# comcon_version_av2.net
KiCad netlist of a schematic drawn in EAGLE
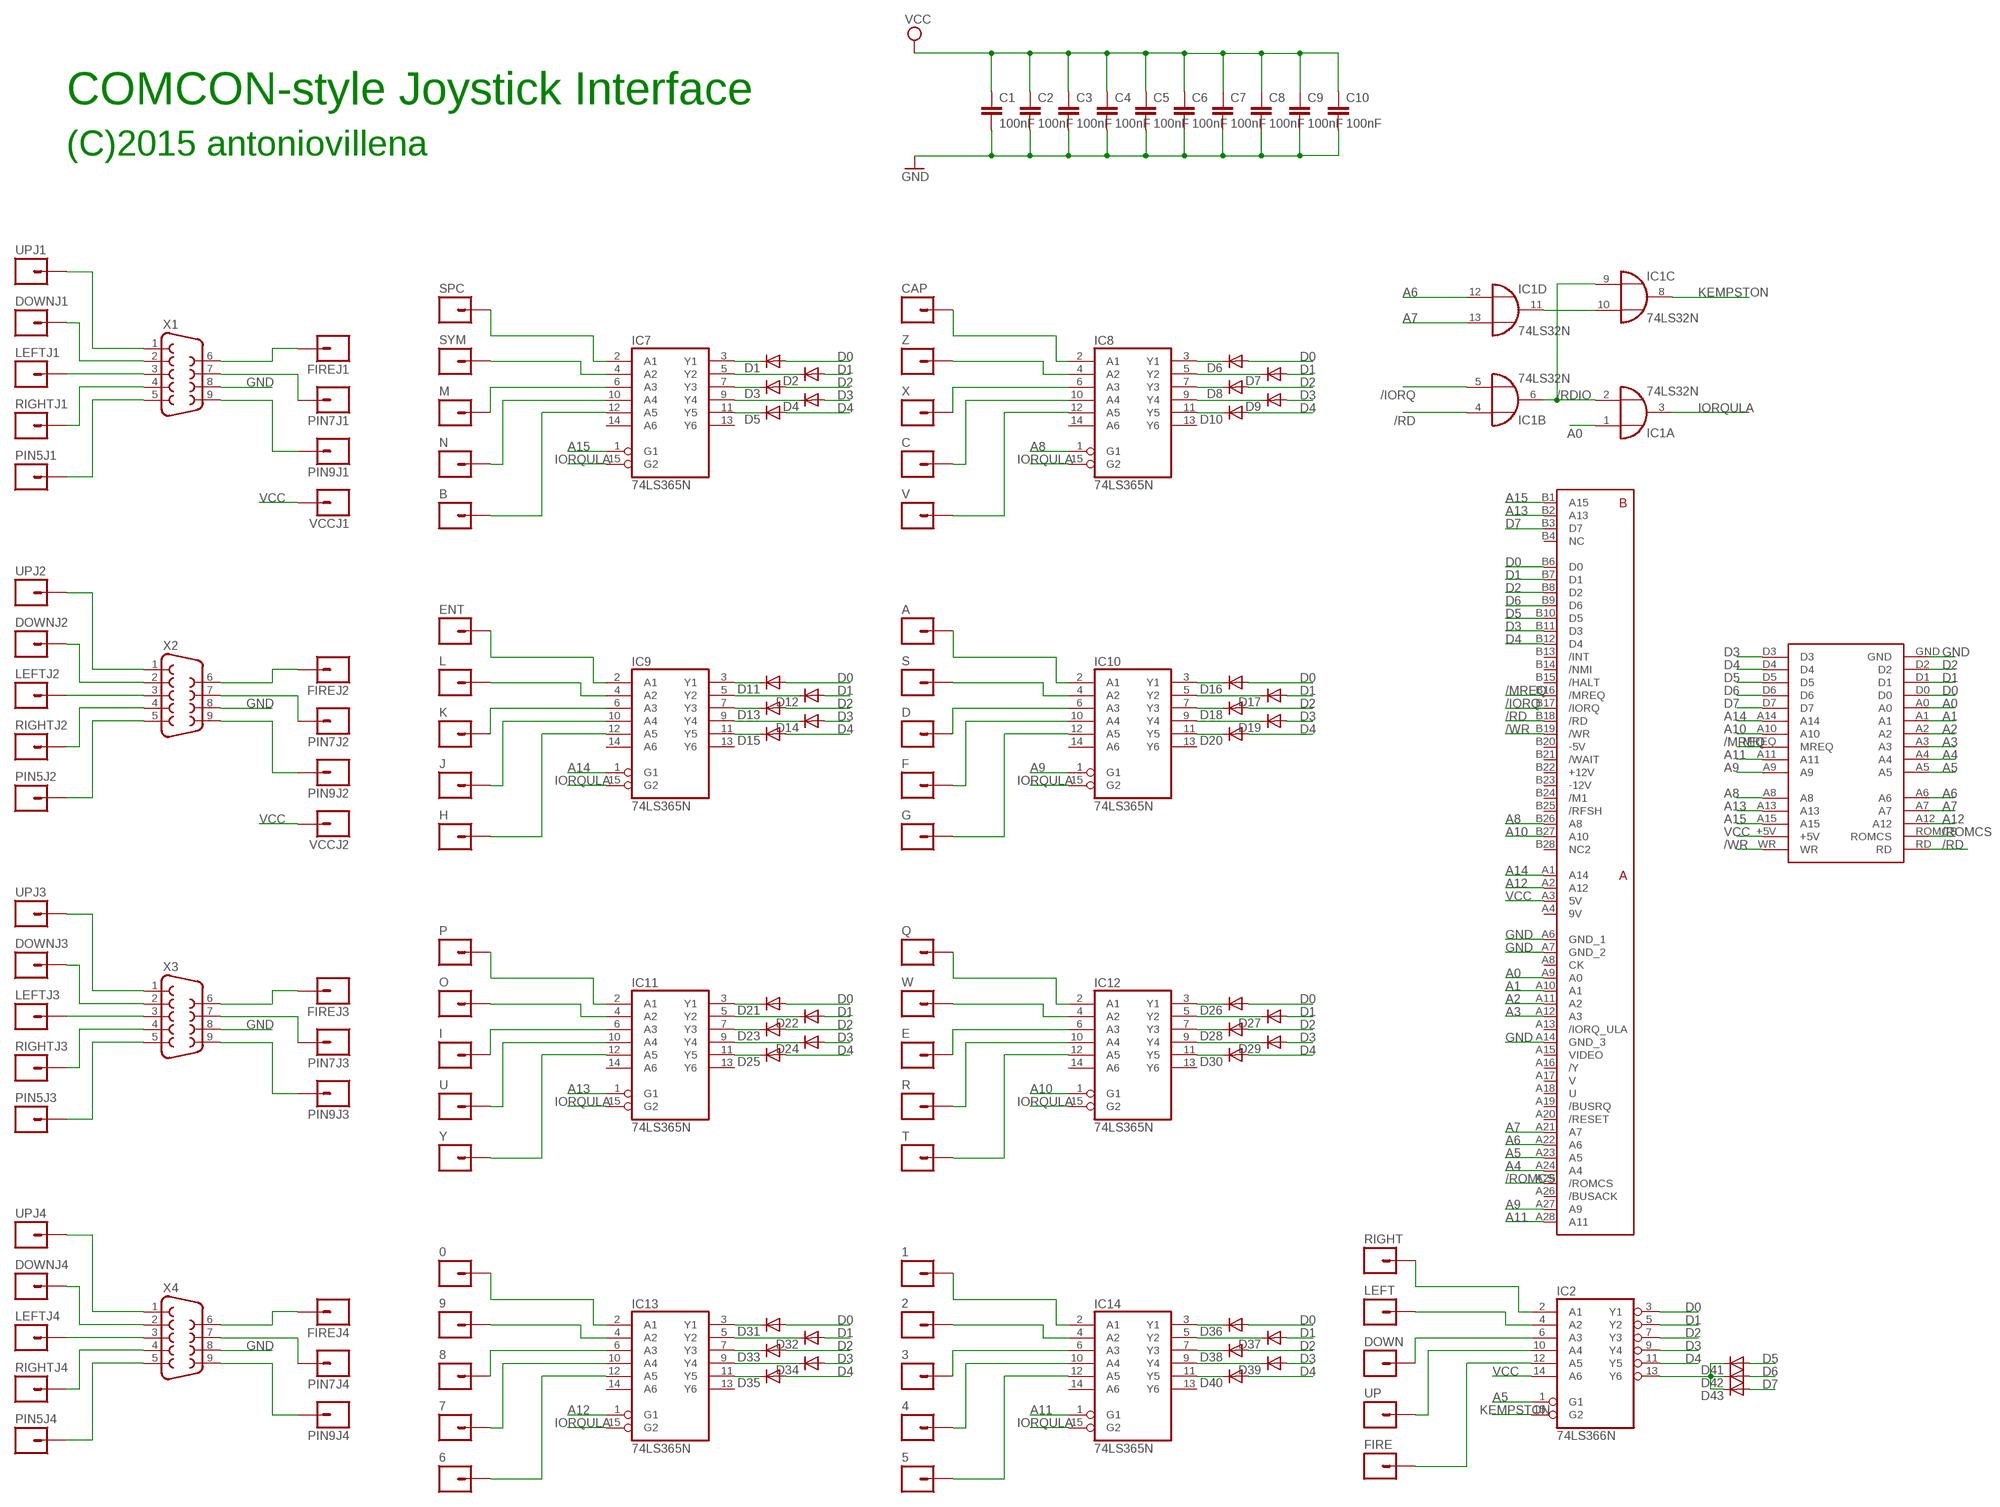
[diagram p0: schematic, sheet 1]

(export (version "E")
  (design (tool "Eeschema 10.0.6"))
  (components
    (comp (ref "0")
      (value "M01PTH")
      (footprint "eagle-import:1X01")
      (libsource (lib "eagle-import") (part "M01PTH"))
    )
    (comp (ref "1")
      (value "M01PTH")
      (footprint "eagle-import:1X01")
      (libsource (lib "eagle-import") (part "M01PTH"))
    )
    (comp (ref "2")
      (value "M01PTH")
      (footprint "eagle-import:1X01")
      (libsource (lib "eagle-import") (part "M01PTH"))
    )
    (comp (ref "3")
      (value "M01PTH")
      (footprint "eagle-import:1X01")
      (libsource (lib "eagle-import") (part "M01PTH"))
    )
    (comp (ref "4")
      (value "M01PTH")
      (footprint "eagle-import:1X01")
      (libsource (lib "eagle-import") (part "M01PTH"))
    )
    (comp (ref "5")
      (value "M01PTH")
      (footprint "eagle-import:1X01")
      (libsource (lib "eagle-import") (part "M01PTH"))
    )
    (comp (ref "6")
      (value "M01PTH")
      (footprint "eagle-import:1X01")
      (libsource (lib "eagle-import") (part "M01PTH"))
    )
    (comp (ref "7")
      (value "M01PTH")
      (footprint "eagle-import:1X01")
      (libsource (lib "eagle-import") (part "M01PTH"))
    )
    (comp (ref "8")
      (value "M01PTH")
      (footprint "eagle-import:1X01")
      (libsource (lib "eagle-import") (part "M01PTH"))
    )
    (comp (ref "9")
      (value "M01PTH")
      (footprint "eagle-import:1X01")
      (libsource (lib "eagle-import") (part "M01PTH"))
    )
    (comp (ref "A")
      (value "M01PTH")
      (footprint "eagle-import:1X01")
      (libsource (lib "eagle-import") (part "M01PTH"))
    )
    (comp (ref "B")
      (value "M01PTH")
      (footprint "eagle-import:1X01")
      (libsource (lib "eagle-import") (part "M01PTH"))
    )
    (comp (ref "C")
      (value "M01PTH")
      (footprint "eagle-import:1X01")
      (libsource (lib "eagle-import") (part "M01PTH"))
    )
    (comp (ref "C1")
      (value "100nF")
      (footprint "eagle-import:C050-025X075")
      (libsource (lib "eagle-import") (part "C-EU050-025X075"))
    )
    (comp (ref "C2")
      (value "100nF")
      (footprint "eagle-import:C050-025X075")
      (libsource (lib "eagle-import") (part "C-EU050-025X075"))
    )
    (comp (ref "C3")
      (value "100nF")
      (footprint "eagle-import:C050-025X075")
      (libsource (lib "eagle-import") (part "C-EU050-025X075"))
    )
    (comp (ref "C4")
      (value "100nF")
      (footprint "eagle-import:C050-025X075")
      (libsource (lib "eagle-import") (part "C-EU050-025X075"))
    )
    (comp (ref "C5")
      (value "100nF")
      (footprint "eagle-import:C050-025X075")
      (libsource (lib "eagle-import") (part "C-EU050-025X075"))
    )
    (comp (ref "C6")
      (value "100nF")
      (footprint "eagle-import:C050-025X075")
      (libsource (lib "eagle-import") (part "C-EU050-025X075"))
    )
    (comp (ref "C7")
      (value "100nF")
      (footprint "eagle-import:C050-025X075")
      (libsource (lib "eagle-import") (part "C-EU050-025X075"))
    )
    (comp (ref "C8")
      (value "100nF")
      (footprint "eagle-import:C050-025X075")
      (libsource (lib "eagle-import") (part "C-EU050-025X075"))
    )
    (comp (ref "C9")
      (value "100nF")
      (footprint "eagle-import:C050-025X075")
      (libsource (lib "eagle-import") (part "C-EU050-025X075"))
    )
    (comp (ref "C10")
      (value "100nF")
      (footprint "eagle-import:C050-025X075")
      (libsource (lib "eagle-import") (part "C-EU050-025X075"))
    )
    (comp (ref "CAP")
      (value "M01PTH")
      (footprint "eagle-import:1X01")
      (libsource (lib "eagle-import") (part "M01PTH"))
    )
    (comp (ref "D")
      (value "M01PTH")
      (footprint "eagle-import:1X01")
      (libsource (lib "eagle-import") (part "M01PTH"))
    )
    (comp (ref "D1")
      (value "1N4148DO35-7")
      (footprint "eagle-import:DO35-7")
      (libsource (lib "eagle-import") (part "1N4148DO35-7"))
    )
    (comp (ref "D2")
      (value "1N4148DO35-7")
      (footprint "eagle-import:DO35-7")
      (libsource (lib "eagle-import") (part "1N4148DO35-7"))
    )
    (comp (ref "D3")
      (value "1N4148DO35-7")
      (footprint "eagle-import:DO35-7")
      (libsource (lib "eagle-import") (part "1N4148DO35-7"))
    )
    (comp (ref "D4")
      (value "1N4148DO35-7")
      (footprint "eagle-import:DO35-7")
      (libsource (lib "eagle-import") (part "1N4148DO35-7"))
    )
    (comp (ref "D5")
      (value "1N4148DO35-7")
      (footprint "eagle-import:DO35-7")
      (libsource (lib "eagle-import") (part "1N4148DO35-7"))
    )
    (comp (ref "D6")
      (value "1N4148DO35-7")
      (footprint "eagle-import:DO35-7")
      (libsource (lib "eagle-import") (part "1N4148DO35-7"))
    )
    (comp (ref "D7")
      (value "1N4148DO35-7")
      (footprint "eagle-import:DO35-7")
      (libsource (lib "eagle-import") (part "1N4148DO35-7"))
    )
    (comp (ref "D8")
      (value "1N4148DO35-7")
      (footprint "eagle-import:DO35-7")
      (libsource (lib "eagle-import") (part "1N4148DO35-7"))
    )
    (comp (ref "D9")
      (value "1N4148DO35-7")
      (footprint "eagle-import:DO35-7")
      (libsource (lib "eagle-import") (part "1N4148DO35-7"))
    )
    (comp (ref "D10")
      (value "1N4148DO35-7")
      (footprint "eagle-import:DO35-7")
      (libsource (lib "eagle-import") (part "1N4148DO35-7"))
    )
    (comp (ref "D11")
      (value "1N4148DO35-7")
      (footprint "eagle-import:DO35-7")
      (libsource (lib "eagle-import") (part "1N4148DO35-7"))
    )
    (comp (ref "D12")
      (value "1N4148DO35-7")
      (footprint "eagle-import:DO35-7")
      (libsource (lib "eagle-import") (part "1N4148DO35-7"))
    )
    (comp (ref "D13")
      (value "1N4148DO35-7")
      (footprint "eagle-import:DO35-7")
      (libsource (lib "eagle-import") (part "1N4148DO35-7"))
    )
    (comp (ref "D14")
      (value "1N4148DO35-7")
      (footprint "eagle-import:DO35-7")
      (libsource (lib "eagle-import") (part "1N4148DO35-7"))
    )
    (comp (ref "D15")
      (value "1N4148DO35-7")
      (footprint "eagle-import:DO35-7")
      (libsource (lib "eagle-import") (part "1N4148DO35-7"))
    )
    (comp (ref "D16")
      (value "1N4148DO35-7")
      (footprint "eagle-import:DO35-7")
      (libsource (lib "eagle-import") (part "1N4148DO35-7"))
    )
    (comp (ref "D17")
      (value "1N4148DO35-7")
      (footprint "eagle-import:DO35-7")
      (libsource (lib "eagle-import") (part "1N4148DO35-7"))
    )
    (comp (ref "D18")
      (value "1N4148DO35-7")
      (footprint "eagle-import:DO35-7")
      (libsource (lib "eagle-import") (part "1N4148DO35-7"))
    )
    (comp (ref "D19")
      (value "1N4148DO35-7")
      (footprint "eagle-import:DO35-7")
      (libsource (lib "eagle-import") (part "1N4148DO35-7"))
    )
    (comp (ref "D20")
      (value "1N4148DO35-7")
      (footprint "eagle-import:DO35-7")
      (libsource (lib "eagle-import") (part "1N4148DO35-7"))
    )
    (comp (ref "D21")
      (value "1N4148DO35-7")
      (footprint "eagle-import:DO35-7")
      (libsource (lib "eagle-import") (part "1N4148DO35-7"))
    )
    (comp (ref "D22")
      (value "1N4148DO35-7")
      (footprint "eagle-import:DO35-7")
      (libsource (lib "eagle-import") (part "1N4148DO35-7"))
    )
    (comp (ref "D23")
      (value "1N4148DO35-7")
      (footprint "eagle-import:DO35-7")
      (libsource (lib "eagle-import") (part "1N4148DO35-7"))
    )
    (comp (ref "D24")
      (value "1N4148DO35-7")
      (footprint "eagle-import:DO35-7")
      (libsource (lib "eagle-import") (part "1N4148DO35-7"))
    )
    (comp (ref "D25")
      (value "1N4148DO35-7")
      (footprint "eagle-import:DO35-7")
      (libsource (lib "eagle-import") (part "1N4148DO35-7"))
    )
    (comp (ref "D26")
      (value "1N4148DO35-7")
      (footprint "eagle-import:DO35-7")
      (libsource (lib "eagle-import") (part "1N4148DO35-7"))
    )
    (comp (ref "D27")
      (value "1N4148DO35-7")
      (footprint "eagle-import:DO35-7")
      (libsource (lib "eagle-import") (part "1N4148DO35-7"))
    )
    (comp (ref "D28")
      (value "1N4148DO35-7")
      (footprint "eagle-import:DO35-7")
      (libsource (lib "eagle-import") (part "1N4148DO35-7"))
    )
    (comp (ref "D29")
      (value "1N4148DO35-7")
      (footprint "eagle-import:DO35-7")
      (libsource (lib "eagle-import") (part "1N4148DO35-7"))
    )
    (comp (ref "D30")
      (value "1N4148DO35-7")
      (footprint "eagle-import:DO35-7")
      (libsource (lib "eagle-import") (part "1N4148DO35-7"))
    )
    (comp (ref "D31")
      (value "1N4148DO35-7")
      (footprint "eagle-import:DO35-7")
      (libsource (lib "eagle-import") (part "1N4148DO35-7"))
    )
    (comp (ref "D32")
      (value "1N4148DO35-7")
      (footprint "eagle-import:DO35-7")
      (libsource (lib "eagle-import") (part "1N4148DO35-7"))
    )
    (comp (ref "D33")
      (value "1N4148DO35-7")
      (footprint "eagle-import:DO35-7")
      (libsource (lib "eagle-import") (part "1N4148DO35-7"))
    )
    (comp (ref "D34")
      (value "1N4148DO35-7")
      (footprint "eagle-import:DO35-7")
      (libsource (lib "eagle-import") (part "1N4148DO35-7"))
    )
    (comp (ref "D35")
      (value "1N4148DO35-7")
      (footprint "eagle-import:DO35-7")
      (libsource (lib "eagle-import") (part "1N4148DO35-7"))
    )
    (comp (ref "D36")
      (value "1N4148DO35-7")
      (footprint "eagle-import:DO35-7")
      (libsource (lib "eagle-import") (part "1N4148DO35-7"))
    )
    (comp (ref "D37")
      (value "1N4148DO35-7")
      (footprint "eagle-import:DO35-7")
      (libsource (lib "eagle-import") (part "1N4148DO35-7"))
    )
    (comp (ref "D38")
      (value "1N4148DO35-7")
      (footprint "eagle-import:DO35-7")
      (libsource (lib "eagle-import") (part "1N4148DO35-7"))
    )
    (comp (ref "D39")
      (value "1N4148DO35-7")
      (footprint "eagle-import:DO35-7")
      (libsource (lib "eagle-import") (part "1N4148DO35-7"))
    )
    (comp (ref "D40")
      (value "1N4148DO35-7")
      (footprint "eagle-import:DO35-7")
      (libsource (lib "eagle-import") (part "1N4148DO35-7"))
    )
    (comp (ref "D41")
      (value "1N4148DO35-10")
      (footprint "eagle-import:DO35-10")
      (libsource (lib "eagle-import") (part "1N4148DO35-10"))
    )
    (comp (ref "D42")
      (value "1N4148DO35-10")
      (footprint "eagle-import:DO35-10")
      (libsource (lib "eagle-import") (part "1N4148DO35-10"))
    )
    (comp (ref "D43")
      (value "1N4148DO35-7")
      (footprint "eagle-import:DO35-7")
      (libsource (lib "eagle-import") (part "1N4148DO35-7"))
    )
    (comp (ref "DOWN")
      (value "M01PTH")
      (footprint "eagle-import:1X01")
      (libsource (lib "eagle-import") (part "M01PTH"))
    )
    (comp (ref "DOWNJ1")
      (value "M01PTH")
      (footprint "eagle-import:1X01")
      (libsource (lib "eagle-import") (part "M01PTH"))
    )
    (comp (ref "DOWNJ2")
      (value "M01PTH")
      (footprint "eagle-import:1X01")
      (libsource (lib "eagle-import") (part "M01PTH"))
    )
    (comp (ref "DOWNJ3")
      (value "M01PTH")
      (footprint "eagle-import:1X01")
      (libsource (lib "eagle-import") (part "M01PTH"))
    )
    (comp (ref "DOWNJ4")
      (value "M01PTH")
      (footprint "eagle-import:1X01")
      (libsource (lib "eagle-import") (part "M01PTH"))
    )
    (comp (ref "E")
      (value "M01PTH")
      (footprint "eagle-import:1X01")
      (libsource (lib "eagle-import") (part "M01PTH"))
    )
    (comp (ref "ENT")
      (value "M01PTH")
      (footprint "eagle-import:1X01")
      (libsource (lib "eagle-import") (part "M01PTH"))
    )
    (comp (ref "F")
      (value "M01PTH")
      (footprint "eagle-import:1X01")
      (libsource (lib "eagle-import") (part "M01PTH"))
    )
    (comp (ref "FIRE")
      (value "M01PTH")
      (footprint "eagle-import:1X01")
      (libsource (lib "eagle-import") (part "M01PTH"))
    )
    (comp (ref "FIREJ1")
      (value "M01PTH")
      (footprint "eagle-import:1X01")
      (libsource (lib "eagle-import") (part "M01PTH"))
    )
    (comp (ref "FIREJ2")
      (value "M01PTH")
      (footprint "eagle-import:1X01")
      (libsource (lib "eagle-import") (part "M01PTH"))
    )
    (comp (ref "FIREJ3")
      (value "M01PTH")
      (footprint "eagle-import:1X01")
      (libsource (lib "eagle-import") (part "M01PTH"))
    )
    (comp (ref "FIREJ4")
      (value "M01PTH")
      (footprint "eagle-import:1X01")
      (libsource (lib "eagle-import") (part "M01PTH"))
    )
    (comp (ref "G")
      (value "M01PTH")
      (footprint "eagle-import:1X01")
      (libsource (lib "eagle-import") (part "M01PTH"))
    )
    (comp (ref "H")
      (value "M01PTH")
      (footprint "eagle-import:1X01")
      (libsource (lib "eagle-import") (part "M01PTH"))
    )
    (comp (ref "I")
      (value "M01PTH")
      (footprint "eagle-import:1X01")
      (libsource (lib "eagle-import") (part "M01PTH"))
    )
    (comp (ref "IC1")
      (value "74LS32N")
      (footprint "eagle-import:DIL14")
      (libsource (lib "eagle-import") (part "7432NLS"))
    )
    (comp (ref "IC2")
      (value "74LS366N")
      (footprint "eagle-import:DIL16")
      (libsource (lib "eagle-import") (part "74366NLS"))
    )
    (comp (ref "IC7")
      (value "74LS365N")
      (footprint "eagle-import:DIL16")
      (libsource (lib "eagle-import") (part "74365NHC"))
    )
    (comp (ref "IC8")
      (value "74LS365N")
      (footprint "eagle-import:DIL16")
      (libsource (lib "eagle-import") (part "74365NHC"))
    )
    (comp (ref "IC9")
      (value "74LS365N")
      (footprint "eagle-import:DIL16")
      (libsource (lib "eagle-import") (part "74365NHC"))
    )
    (comp (ref "IC10")
      (value "74LS365N")
      (footprint "eagle-import:DIL16")
      (libsource (lib "eagle-import") (part "74365NHC"))
    )
    (comp (ref "IC11")
      (value "74LS365N")
      (footprint "eagle-import:DIL16")
      (libsource (lib "eagle-import") (part "74365NHC"))
    )
    (comp (ref "IC12")
      (value "74LS365N")
      (footprint "eagle-import:DIL16")
      (libsource (lib "eagle-import") (part "74365NHC"))
    )
    (comp (ref "IC13")
      (value "74LS365N")
      (footprint "eagle-import:DIL16")
      (libsource (lib "eagle-import") (part "74365NHC"))
    )
    (comp (ref "IC14")
      (value "74LS365N")
      (footprint "eagle-import:DIL16")
      (libsource (lib "eagle-import") (part "74365NHC"))
    )
    (comp (ref "J")
      (value "M01PTH")
      (footprint "eagle-import:1X01")
      (libsource (lib "eagle-import") (part "M01PTH"))
    )
    (comp (ref "K")
      (value "M01PTH")
      (footprint "eagle-import:1X01")
      (libsource (lib "eagle-import") (part "M01PTH"))
    )
    (comp (ref "L")
      (value "M01PTH")
      (footprint "eagle-import:1X01")
      (libsource (lib "eagle-import") (part "M01PTH"))
    )
    (comp (ref "LEFT")
      (value "M01PTH")
      (footprint "eagle-import:1X01")
      (libsource (lib "eagle-import") (part "M01PTH"))
    )
    (comp (ref "LEFTJ1")
      (value "M01PTH")
      (footprint "eagle-import:1X01")
      (libsource (lib "eagle-import") (part "M01PTH"))
    )
    (comp (ref "LEFTJ2")
      (value "M01PTH")
      (footprint "eagle-import:1X01")
      (libsource (lib "eagle-import") (part "M01PTH"))
    )
    (comp (ref "LEFTJ3")
      (value "M01PTH")
      (footprint "eagle-import:1X01")
      (libsource (lib "eagle-import") (part "M01PTH"))
    )
    (comp (ref "LEFTJ4")
      (value "M01PTH")
      (footprint "eagle-import:1X01")
      (libsource (lib "eagle-import") (part "M01PTH"))
    )
    (comp (ref "M")
      (value "M01PTH")
      (footprint "eagle-import:1X01")
      (libsource (lib "eagle-import") (part "M01PTH"))
    )
    (comp (ref "N")
      (value "M01PTH")
      (footprint "eagle-import:1X01")
      (libsource (lib "eagle-import") (part "M01PTH"))
    )
    (comp (ref "O")
      (value "M01PTH")
      (footprint "eagle-import:1X01")
      (libsource (lib "eagle-import") (part "M01PTH"))
    )
    (comp (ref "P")
      (value "M01PTH")
      (footprint "eagle-import:1X01")
      (libsource (lib "eagle-import") (part "M01PTH"))
    )
    (comp (ref "PIN5J1")
      (value "M01PTH")
      (footprint "eagle-import:1X01")
      (libsource (lib "eagle-import") (part "M01PTH"))
    )
    (comp (ref "PIN5J2")
      (value "M01PTH")
      (footprint "eagle-import:1X01")
      (libsource (lib "eagle-import") (part "M01PTH"))
    )
    (comp (ref "PIN5J3")
      (value "M01PTH")
      (footprint "eagle-import:1X01")
      (libsource (lib "eagle-import") (part "M01PTH"))
    )
    (comp (ref "PIN5J4")
      (value "M01PTH")
      (footprint "eagle-import:1X01")
      (libsource (lib "eagle-import") (part "M01PTH"))
    )
    (comp (ref "PIN7J1")
      (value "M01PTH")
      (footprint "eagle-import:1X01")
      (libsource (lib "eagle-import") (part "M01PTH"))
    )
    (comp (ref "PIN7J2")
      (value "M01PTH")
      (footprint "eagle-import:1X01")
      (libsource (lib "eagle-import") (part "M01PTH"))
    )
    (comp (ref "PIN7J3")
      (value "M01PTH")
      (footprint "eagle-import:1X01")
      (libsource (lib "eagle-import") (part "M01PTH"))
    )
    (comp (ref "PIN7J4")
      (value "M01PTH")
      (footprint "eagle-import:1X01")
      (libsource (lib "eagle-import") (part "M01PTH"))
    )
    (comp (ref "PIN9J1")
      (value "M01PTH")
      (footprint "eagle-import:1X01")
      (libsource (lib "eagle-import") (part "M01PTH"))
    )
    (comp (ref "PIN9J2")
      (value "M01PTH")
      (footprint "eagle-import:1X01")
      (libsource (lib "eagle-import") (part "M01PTH"))
    )
    (comp (ref "PIN9J3")
      (value "M01PTH")
      (footprint "eagle-import:1X01")
      (libsource (lib "eagle-import") (part "M01PTH"))
    )
    (comp (ref "PIN9J4")
      (value "M01PTH")
      (footprint "eagle-import:1X01")
      (libsource (lib "eagle-import") (part "M01PTH"))
    )
    (comp (ref "Q")
      (value "M01PTH")
      (footprint "eagle-import:1X01")
      (libsource (lib "eagle-import") (part "M01PTH"))
    )
    (comp (ref "R")
      (value "M01PTH")
      (footprint "eagle-import:1X01")
      (libsource (lib "eagle-import") (part "M01PTH"))
    )
    (comp (ref "RIGHT")
      (value "M01PTH")
      (footprint "eagle-import:1X01")
      (libsource (lib "eagle-import") (part "M01PTH"))
    )
    (comp (ref "RIGHTJ1")
      (value "M01PTH")
      (footprint "eagle-import:1X01")
      (libsource (lib "eagle-import") (part "M01PTH"))
    )
    (comp (ref "RIGHTJ2")
      (value "M01PTH")
      (footprint "eagle-import:1X01")
      (libsource (lib "eagle-import") (part "M01PTH"))
    )
    (comp (ref "RIGHTJ3")
      (value "M01PTH")
      (footprint "eagle-import:1X01")
      (libsource (lib "eagle-import") (part "M01PTH"))
    )
    (comp (ref "RIGHTJ4")
      (value "M01PTH")
      (footprint "eagle-import:1X01")
      (libsource (lib "eagle-import") (part "M01PTH"))
    )
    (comp (ref "S")
      (value "M01PTH")
      (footprint "eagle-import:1X01")
      (libsource (lib "eagle-import") (part "M01PTH"))
    )
    (comp (ref "SPC")
      (value "M01PTH")
      (footprint "eagle-import:1X01")
      (libsource (lib "eagle-import") (part "M01PTH"))
    )
    (comp (ref "SYM")
      (value "M01PTH")
      (footprint "eagle-import:1X01")
      (libsource (lib "eagle-import") (part "M01PTH"))
    )
    (comp (ref "T")
      (value "M01PTH")
      (footprint "eagle-import:1X01")
      (libsource (lib "eagle-import") (part "M01PTH"))
    )
    (comp (ref "U")
      (value "M01PTH")
      (footprint "eagle-import:1X01")
      (libsource (lib "eagle-import") (part "M01PTH"))
    )
    (comp (ref "U$1")
      (value "ZX_CARTRIDGE")
      (footprint "eagle-import:ZX_CARTRIDGE")
      (libsource (lib "eagle-import") (part "ZX_CARTRIDGE"))
    )
    (comp (ref "U$3")
      (value "ZXSP_ED2X28_SPE")
      (footprint "eagle-import:2X28_SPE")
      (libsource (lib "eagle-import") (part "ZXSP_ED2X28_SPE"))
    )
    (comp (ref "UP")
      (value "M01PTH")
      (footprint "eagle-import:1X01")
      (libsource (lib "eagle-import") (part "M01PTH"))
    )
    (comp (ref "UPJ1")
      (value "M01PTH")
      (footprint "eagle-import:1X01")
      (libsource (lib "eagle-import") (part "M01PTH"))
    )
    (comp (ref "UPJ2")
      (value "M01PTH")
      (footprint "eagle-import:1X01")
      (libsource (lib "eagle-import") (part "M01PTH"))
    )
    (comp (ref "UPJ3")
      (value "M01PTH")
      (footprint "eagle-import:1X01")
      (libsource (lib "eagle-import") (part "M01PTH"))
    )
    (comp (ref "UPJ4")
      (value "M01PTH")
      (footprint "eagle-import:1X01")
      (libsource (lib "eagle-import") (part "M01PTH"))
    )
    (comp (ref "V")
      (value "M01PTH")
      (footprint "eagle-import:1X01")
      (libsource (lib "eagle-import") (part "M01PTH"))
    )
    (comp (ref "VCCJ1")
      (value "M01PTH")
      (footprint "eagle-import:1X01")
      (libsource (lib "eagle-import") (part "M01PTH"))
    )
    (comp (ref "VCCJ2")
      (value "M01PTH")
      (footprint "eagle-import:1X01")
      (libsource (lib "eagle-import") (part "M01PTH"))
    )
    (comp (ref "W")
      (value "M01PTH")
      (footprint "eagle-import:1X01")
      (libsource (lib "eagle-import") (part "M01PTH"))
    )
    (comp (ref "X")
      (value "M01PTH")
      (footprint "eagle-import:1X01")
      (libsource (lib "eagle-import") (part "M01PTH"))
    )
    (comp (ref "X1")
      (value "F09D")
      (footprint "eagle-import:F09D")
      (libsource (lib "eagle-import") (part "F09D"))
    )
    (comp (ref "X2")
      (value "F09D")
      (footprint "eagle-import:F09D")
      (libsource (lib "eagle-import") (part "F09D"))
    )
    (comp (ref "X3")
      (value "F09D")
      (footprint "eagle-import:F09D")
      (libsource (lib "eagle-import") (part "F09D"))
    )
    (comp (ref "X4")
      (value "F09D")
      (footprint "eagle-import:F09D")
      (libsource (lib "eagle-import") (part "F09D"))
    )
    (comp (ref "Y")
      (value "M01PTH")
      (footprint "eagle-import:1X01")
      (libsource (lib "eagle-import") (part "M01PTH"))
    )
    (comp (ref "Z")
      (value "M01PTH")
      (footprint "eagle-import:1X01")
      (libsource (lib "eagle-import") (part "M01PTH"))
    )
  )
  (nets
    (net (code "1") (name "/+12V") (class "Default")
      (node (ref "U$3") (pin "B22") (pinfunction "+12V_B22") (pintype "power_in"))
    )
    (net (code "2") (name "/-5V") (class "Default")
      (node (ref "U$3") (pin "B20") (pinfunction "-5V_B20") (pintype "power_in"))
    )
    (net (code "3") (name "/-12V") (class "Default")
      (node (ref "U$3") (pin "B23") (pinfunction "-12V_B23") (pintype "power_in"))
    )
    (net (code "4") (name "/9V") (class "Default")
      (node (ref "U$3") (pin "A4") (pinfunction "9V_A4") (pintype "power_in"))
    )
    (net (code "5") (name "/A0") (class "Default")
      (node (ref "IC1") (pin "1") (pinfunction "I0_1") (pintype "input"))
      (node (ref "U$1") (pin "A0") (pinfunction "A0_A0") (pintype "bidirectional"))
      (node (ref "U$3") (pin "A9") (pinfunction "A0_A9") (pintype "bidirectional"))
    )
    (net (code "6") (name "/A1") (class "Default")
      (node (ref "U$1") (pin "A1") (pinfunction "A1_A1") (pintype "bidirectional"))
      (node (ref "U$3") (pin "A10") (pinfunction "A1_A10") (pintype "bidirectional"))
    )
    (net (code "7") (name "/A2") (class "Default")
      (node (ref "U$1") (pin "A2") (pinfunction "A2_A2") (pintype "bidirectional"))
      (node (ref "U$3") (pin "A11") (pinfunction "A2_A11") (pintype "bidirectional"))
    )
    (net (code "8") (name "/A3") (class "Default")
      (node (ref "U$1") (pin "A3") (pinfunction "A3_A3") (pintype "bidirectional"))
      (node (ref "U$3") (pin "A12") (pinfunction "A3_A12") (pintype "bidirectional"))
    )
    (net (code "9") (name "/A4") (class "Default")
      (node (ref "U$1") (pin "A4") (pinfunction "A4_A4") (pintype "bidirectional"))
      (node (ref "U$3") (pin "A24") (pinfunction "A4_A24") (pintype "bidirectional"))
    )
    (net (code "10") (name "/A5") (class "Default")
      (node (ref "IC2") (pin "1") (pinfunction "G1_1") (pintype "input"))
      (node (ref "U$1") (pin "A5") (pinfunction "A5_A5") (pintype "bidirectional"))
      (node (ref "U$3") (pin "A23") (pinfunction "A5_A23") (pintype "bidirectional"))
    )
    (net (code "11") (name "/A6") (class "Default")
      (node (ref "IC1") (pin "12") (pinfunction "I0_12") (pintype "input"))
      (node (ref "U$1") (pin "A6") (pinfunction "A6_A6") (pintype "bidirectional"))
      (node (ref "U$3") (pin "A22") (pinfunction "A6_A22") (pintype "bidirectional"))
    )
    (net (code "12") (name "/A7") (class "Default")
      (node (ref "IC1") (pin "13") (pinfunction "I1_13") (pintype "input"))
      (node (ref "U$1") (pin "A7") (pinfunction "A7_A7") (pintype "bidirectional"))
      (node (ref "U$3") (pin "A21") (pinfunction "A7_A21") (pintype "bidirectional"))
    )
    (net (code "13") (name "/A8") (class "Default")
      (node (ref "IC8") (pin "1") (pinfunction "G1_1") (pintype "input"))
      (node (ref "U$1") (pin "A8") (pinfunction "A8_A8") (pintype "bidirectional"))
      (node (ref "U$3") (pin "B26") (pinfunction "A8_B26") (pintype "bidirectional"))
    )
    (net (code "14") (name "/A9") (class "Default")
      (node (ref "IC10") (pin "1") (pinfunction "G1_1") (pintype "input"))
      (node (ref "U$1") (pin "A9") (pinfunction "A9_A9") (pintype "bidirectional"))
      (node (ref "U$3") (pin "A27") (pinfunction "A9_A27") (pintype "bidirectional"))
    )
    (net (code "15") (name "/A10") (class "Default")
      (node (ref "IC12") (pin "1") (pinfunction "G1_1") (pintype "input"))
      (node (ref "U$1") (pin "A10") (pinfunction "A10_A10") (pintype "bidirectional"))
      (node (ref "U$3") (pin "B27") (pinfunction "A10_B27") (pintype "bidirectional"))
    )
    (net (code "16") (name "/A11") (class "Default")
      (node (ref "IC14") (pin "1") (pinfunction "G1_1") (pintype "input"))
      (node (ref "U$1") (pin "A11") (pinfunction "A11_A11") (pintype "bidirectional"))
      (node (ref "U$3") (pin "A28") (pinfunction "A11_A28") (pintype "bidirectional"))
    )
    (net (code "17") (name "/A12") (class "Default")
      (node (ref "IC13") (pin "1") (pinfunction "G1_1") (pintype "input"))
      (node (ref "U$1") (pin "A12") (pinfunction "A12_A12") (pintype "bidirectional"))
      (node (ref "U$3") (pin "A2") (pinfunction "A12_A2") (pintype "bidirectional"))
    )
    (net (code "18") (name "/A13") (class "Default")
      (node (ref "IC11") (pin "1") (pinfunction "G1_1") (pintype "input"))
      (node (ref "U$1") (pin "A13") (pinfunction "A13_A13") (pintype "bidirectional"))
      (node (ref "U$3") (pin "B2") (pinfunction "A13_B2") (pintype "bidirectional"))
    )
    (net (code "19") (name "/A14") (class "Default")
      (node (ref "IC9") (pin "1") (pinfunction "G1_1") (pintype "input"))
      (node (ref "U$1") (pin "A14") (pinfunction "A14_A14") (pintype "bidirectional"))
      (node (ref "U$3") (pin "A1") (pinfunction "A14_A1") (pintype "bidirectional"))
    )
    (net (code "20") (name "/A15") (class "Default")
      (node (ref "IC7") (pin "1") (pinfunction "G1_1") (pintype "input"))
      (node (ref "U$1") (pin "A15") (pinfunction "A15_A15") (pintype "bidirectional"))
      (node (ref "U$3") (pin "B1") (pinfunction "A15_B1") (pintype "bidirectional"))
    )
    (net (code "21") (name "/D0") (class "Default")
      (node (ref "D1") (pin "A") (pinfunction "A_A") (pintype "passive"))
      (node (ref "D11") (pin "A") (pinfunction "A_A") (pintype "passive"))
      (node (ref "D16") (pin "A") (pinfunction "A_A") (pintype "passive"))
      (node (ref "D21") (pin "A") (pinfunction "A_A") (pintype "passive"))
      (node (ref "D26") (pin "A") (pinfunction "A_A") (pintype "passive"))
      (node (ref "D31") (pin "A") (pinfunction "A_A") (pintype "passive"))
      (node (ref "D36") (pin "A") (pinfunction "A_A") (pintype "passive"))
      (node (ref "D6") (pin "A") (pinfunction "A_A") (pintype "passive"))
      (node (ref "IC2") (pin "3") (pinfunction "Y1_3") (pintype "tri_state"))
      (node (ref "U$1") (pin "D0") (pinfunction "D0_D0") (pintype "bidirectional"))
      (node (ref "U$3") (pin "B6") (pinfunction "D0_B6") (pintype "bidirectional"))
    )
    (net (code "22") (name "/D1") (class "Default")
      (node (ref "D12") (pin "A") (pinfunction "A_A") (pintype "passive"))
      (node (ref "D17") (pin "A") (pinfunction "A_A") (pintype "passive"))
      (node (ref "D2") (pin "A") (pinfunction "A_A") (pintype "passive"))
      (node (ref "D22") (pin "A") (pinfunction "A_A") (pintype "passive"))
      (node (ref "D27") (pin "A") (pinfunction "A_A") (pintype "passive"))
      (node (ref "D32") (pin "A") (pinfunction "A_A") (pintype "passive"))
      (node (ref "D37") (pin "A") (pinfunction "A_A") (pintype "passive"))
      (node (ref "D7") (pin "A") (pinfunction "A_A") (pintype "passive"))
      (node (ref "IC2") (pin "5") (pinfunction "Y2_5") (pintype "tri_state"))
      (node (ref "U$1") (pin "D1") (pinfunction "D1_D1") (pintype "bidirectional"))
      (node (ref "U$3") (pin "B7") (pinfunction "D1_B7") (pintype "bidirectional"))
    )
    (net (code "23") (name "/D2") (class "Default")
      (node (ref "D13") (pin "A") (pinfunction "A_A") (pintype "passive"))
      (node (ref "D18") (pin "A") (pinfunction "A_A") (pintype "passive"))
      (node (ref "D23") (pin "A") (pinfunction "A_A") (pintype "passive"))
      (node (ref "D28") (pin "A") (pinfunction "A_A") (pintype "passive"))
      (node (ref "D3") (pin "A") (pinfunction "A_A") (pintype "passive"))
      (node (ref "D33") (pin "A") (pinfunction "A_A") (pintype "passive"))
      (node (ref "D38") (pin "A") (pinfunction "A_A") (pintype "passive"))
      (node (ref "D8") (pin "A") (pinfunction "A_A") (pintype "passive"))
      (node (ref "IC2") (pin "7") (pinfunction "Y3_7") (pintype "tri_state"))
      (node (ref "U$1") (pin "D2") (pinfunction "D2_D2") (pintype "bidirectional"))
      (node (ref "U$3") (pin "B8") (pinfunction "D2_B8") (pintype "bidirectional"))
    )
    (net (code "24") (name "/D3") (class "Default")
      (node (ref "D14") (pin "A") (pinfunction "A_A") (pintype "passive"))
      (node (ref "D19") (pin "A") (pinfunction "A_A") (pintype "passive"))
      (node (ref "D24") (pin "A") (pinfunction "A_A") (pintype "passive"))
      (node (ref "D29") (pin "A") (pinfunction "A_A") (pintype "passive"))
      (node (ref "D34") (pin "A") (pinfunction "A_A") (pintype "passive"))
      (node (ref "D39") (pin "A") (pinfunction "A_A") (pintype "passive"))
      (node (ref "D4") (pin "A") (pinfunction "A_A") (pintype "passive"))
      (node (ref "D9") (pin "A") (pinfunction "A_A") (pintype "passive"))
      (node (ref "IC2") (pin "9") (pinfunction "Y4_9") (pintype "tri_state"))
      (node (ref "U$1") (pin "D3") (pinfunction "D3_D3") (pintype "bidirectional"))
      (node (ref "U$3") (pin "B11") (pinfunction "D3_B11") (pintype "bidirectional"))
    )
    (net (code "25") (name "/D4") (class "Default")
      (node (ref "D10") (pin "A") (pinfunction "A_A") (pintype "passive"))
      (node (ref "D15") (pin "A") (pinfunction "A_A") (pintype "passive"))
      (node (ref "D20") (pin "A") (pinfunction "A_A") (pintype "passive"))
      (node (ref "D25") (pin "A") (pinfunction "A_A") (pintype "passive"))
      (node (ref "D30") (pin "A") (pinfunction "A_A") (pintype "passive"))
      (node (ref "D35") (pin "A") (pinfunction "A_A") (pintype "passive"))
      (node (ref "D40") (pin "A") (pinfunction "A_A") (pintype "passive"))
      (node (ref "D5") (pin "A") (pinfunction "A_A") (pintype "passive"))
      (node (ref "IC2") (pin "11") (pinfunction "Y5_11") (pintype "tri_state"))
      (node (ref "U$1") (pin "D4") (pinfunction "D4_D4") (pintype "bidirectional"))
      (node (ref "U$3") (pin "B12") (pinfunction "D4_B12") (pintype "bidirectional"))
    )
    (net (code "26") (name "/D5") (class "Default")
      (node (ref "D41") (pin "A") (pinfunction "A_A") (pintype "passive"))
      (node (ref "U$1") (pin "D5") (pinfunction "D5_D5") (pintype "bidirectional"))
      (node (ref "U$3") (pin "B10") (pinfunction "D5_B10") (pintype "bidirectional"))
    )
    (net (code "27") (name "/D6") (class "Default")
      (node (ref "D42") (pin "A") (pinfunction "A_A") (pintype "passive"))
      (node (ref "U$1") (pin "D6") (pinfunction "D6_D6") (pintype "bidirectional"))
      (node (ref "U$3") (pin "B9") (pinfunction "D6_B9") (pintype "bidirectional"))
    )
    (net (code "28") (name "/D7") (class "Default")
      (node (ref "D43") (pin "A") (pinfunction "A_A") (pintype "passive"))
      (node (ref "U$1") (pin "D7") (pinfunction "D7_D7") (pintype "bidirectional"))
      (node (ref "U$3") (pin "B3") (pinfunction "D7_B3") (pintype "bidirectional"))
    )
    (net (code "29") (name "/IORQULA") (class "Default")
      (node (ref "IC1") (pin "3") (pinfunction "O_3") (pintype "output"))
      (node (ref "IC10") (pin "15") (pinfunction "G2_15") (pintype "input"))
      (node (ref "IC11") (pin "15") (pinfunction "G2_15") (pintype "input"))
      (node (ref "IC12") (pin "15") (pinfunction "G2_15") (pintype "input"))
      (node (ref "IC13") (pin "15") (pinfunction "G2_15") (pintype "input"))
      (node (ref "IC14") (pin "15") (pinfunction "G2_15") (pintype "input"))
      (node (ref "IC7") (pin "15") (pinfunction "G2_15") (pintype "input"))
      (node (ref "IC8") (pin "15") (pinfunction "G2_15") (pintype "input"))
      (node (ref "IC9") (pin "15") (pinfunction "G2_15") (pintype "input"))
    )
    (net (code "30") (name "/KEMPSTON") (class "Default")
      (node (ref "IC1") (pin "8") (pinfunction "O_8") (pintype "output"))
      (node (ref "IC2") (pin "15") (pinfunction "G2_15") (pintype "input"))
    )
    (net (code "31") (name "/{slash}IORQ") (class "Default")
      (node (ref "IC1") (pin "5") (pinfunction "I1_5") (pintype "input"))
      (node (ref "U$3") (pin "B17") (pinfunction "/IORQ_B17") (pintype "bidirectional"))
    )
    (net (code "32") (name "/{slash}MREQ") (class "Default")
      (node (ref "U$1") (pin "MREQ") (pinfunction "MREQ_MREQ") (pintype "bidirectional"))
      (node (ref "U$3") (pin "B16") (pinfunction "/MREQ_B16") (pintype "bidirectional"))
    )
    (net (code "33") (name "/{slash}RD") (class "Default")
      (node (ref "IC1") (pin "4") (pinfunction "I0_4") (pintype "input"))
      (node (ref "U$1") (pin "RD") (pinfunction "RD_RD") (pintype "bidirectional"))
      (node (ref "U$3") (pin "B18") (pinfunction "/RD_B18") (pintype "bidirectional"))
    )
    (net (code "34") (name "/{slash}RDIO") (class "Default")
      (node (ref "IC1") (pin "2") (pinfunction "I1_2") (pintype "input"))
      (node (ref "IC1") (pin "6") (pinfunction "O_6") (pintype "output"))
      (node (ref "IC1") (pin "9") (pinfunction "I0_9") (pintype "input"))
    )
    (net (code "35") (name "/{slash}ROMCS") (class "Default")
      (node (ref "U$1") (pin "ROMCS") (pinfunction "ROMCS_ROMCS") (pintype "bidirectional"))
      (node (ref "U$3") (pin "A25") (pinfunction "/ROMCS_A25") (pintype "bidirectional"))
    )
    (net (code "36") (name "/{slash}WR") (class "Default")
      (node (ref "U$1") (pin "WR") (pinfunction "WR_WR") (pintype "bidirectional"))
      (node (ref "U$3") (pin "B19") (pinfunction "/WR_B19") (pintype "bidirectional"))
    )
    (net (code "37") (name "GND") (class "Default")
      (node (ref "C1") (pin "2") (pinfunction "2_2") (pintype "passive"))
      (node (ref "C10") (pin "2") (pinfunction "2_2") (pintype "passive"))
      (node (ref "C2") (pin "2") (pinfunction "2_2") (pintype "passive"))
      (node (ref "C3") (pin "2") (pinfunction "2_2") (pintype "passive"))
      (node (ref "C4") (pin "2") (pinfunction "2_2") (pintype "passive"))
      (node (ref "C5") (pin "2") (pinfunction "2_2") (pintype "passive"))
      (node (ref "C6") (pin "2") (pinfunction "2_2") (pintype "passive"))
      (node (ref "C7") (pin "2") (pinfunction "2_2") (pintype "passive"))
      (node (ref "C8") (pin "2") (pinfunction "2_2") (pintype "passive"))
      (node (ref "C9") (pin "2") (pinfunction "2_2") (pintype "passive"))
      (node (ref "U$1") (pin "GND") (pinfunction "GND_GND") (pintype "bidirectional"))
      (node (ref "U$3") (pin "A14") (pinfunction "GND_3_A14") (pintype "power_in"))
      (node (ref "U$3") (pin "A6") (pinfunction "GND_1_A6") (pintype "power_in"))
      (node (ref "U$3") (pin "A7") (pinfunction "GND_2_A7") (pintype "power_in"))
      (node (ref "X1") (pin "8") (pinfunction "8_8") (pintype "passive"))
      (node (ref "X2") (pin "8") (pinfunction "8_8") (pintype "passive"))
      (node (ref "X3") (pin "8") (pinfunction "8_8") (pintype "passive"))
      (node (ref "X4") (pin "8") (pinfunction "8_8") (pintype "passive"))
    )
    (net (code "38") (name "Net-(DOWNJ1-Pad1)") (class "Default")
      (node (ref "DOWNJ1") (pin "1") (pinfunction "1_1") (pintype "passive"))
      (node (ref "X1") (pin "2") (pinfunction "2_2") (pintype "passive"))
    )
    (net (code "39") (name "Net-(DOWNJ2-Pad1)") (class "Default")
      (node (ref "DOWNJ2") (pin "1") (pinfunction "1_1") (pintype "passive"))
      (node (ref "X2") (pin "2") (pinfunction "2_2") (pintype "passive"))
    )
    (net (code "40") (name "Net-(DOWNJ3-Pad1)") (class "Default")
      (node (ref "DOWNJ3") (pin "1") (pinfunction "1_1") (pintype "passive"))
      (node (ref "X3") (pin "2") (pinfunction "2_2") (pintype "passive"))
    )
    (net (code "41") (name "Net-(DOWNJ4-Pad1)") (class "Default")
      (node (ref "DOWNJ4") (pin "1") (pinfunction "1_1") (pintype "passive"))
      (node (ref "X4") (pin "2") (pinfunction "2_2") (pintype "passive"))
    )
    (net (code "42") (name "Net-(FIREJ1-Pad1)") (class "Default")
      (node (ref "FIREJ1") (pin "1") (pinfunction "1_1") (pintype "passive"))
      (node (ref "X1") (pin "6") (pinfunction "6_6") (pintype "passive"))
    )
    (net (code "43") (name "Net-(FIREJ2-Pad1)") (class "Default")
      (node (ref "FIREJ2") (pin "1") (pinfunction "1_1") (pintype "passive"))
      (node (ref "X2") (pin "6") (pinfunction "6_6") (pintype "passive"))
    )
    (net (code "44") (name "Net-(FIREJ3-Pad1)") (class "Default")
      (node (ref "FIREJ3") (pin "1") (pinfunction "1_1") (pintype "passive"))
      (node (ref "X3") (pin "6") (pinfunction "6_6") (pintype "passive"))
    )
    (net (code "45") (name "Net-(FIREJ4-Pad1)") (class "Default")
      (node (ref "FIREJ4") (pin "1") (pinfunction "1_1") (pintype "passive"))
      (node (ref "X4") (pin "6") (pinfunction "6_6") (pintype "passive"))
    )
    (net (code "46") (name "Net-(IC1C-I1)") (class "Default")
      (node (ref "IC1") (pin "10") (pinfunction "I1_10") (pintype "input"))
      (node (ref "IC1") (pin "11") (pinfunction "O_11") (pintype "output"))
    )
    (net (code "47") (name "Net-(IC2A-A1)") (class "Default")
      (node (ref "IC2") (pin "2") (pinfunction "A1_2") (pintype "input"))
      (node (ref "RIGHT") (pin "1") (pinfunction "1_1") (pintype "passive"))
    )
    (net (code "48") (name "Net-(IC2A-A2)") (class "Default")
      (node (ref "IC2") (pin "4") (pinfunction "A2_4") (pintype "input"))
      (node (ref "LEFT") (pin "1") (pinfunction "1_1") (pintype "passive"))
    )
    (net (code "49") (name "Net-(IC2A-A3)") (class "Default")
      (node (ref "DOWN") (pin "1") (pinfunction "1_1") (pintype "passive"))
      (node (ref "IC2") (pin "6") (pinfunction "A3_6") (pintype "input"))
    )
    (net (code "50") (name "Net-(IC2A-A4)") (class "Default")
      (node (ref "IC2") (pin "10") (pinfunction "A4_10") (pintype "input"))
      (node (ref "UP") (pin "1") (pinfunction "1_1") (pintype "passive"))
    )
    (net (code "51") (name "Net-(IC2A-A5)") (class "Default")
      (node (ref "FIRE") (pin "1") (pinfunction "1_1") (pintype "passive"))
      (node (ref "IC2") (pin "12") (pinfunction "A5_12") (pintype "input"))
    )
    (net (code "52") (name "Net-(IC2A-Y6)") (class "Default")
      (node (ref "D41") (pin "C") (pinfunction "C_C") (pintype "passive"))
      (node (ref "D42") (pin "C") (pinfunction "C_C") (pintype "passive"))
      (node (ref "D43") (pin "C") (pinfunction "C_C") (pintype "passive"))
      (node (ref "IC2") (pin "13") (pinfunction "Y6_13") (pintype "tri_state"))
    )
    (net (code "53") (name "Net-(IC7A-A1)") (class "Default")
      (node (ref "IC7") (pin "2") (pinfunction "A1_2") (pintype "input"))
      (node (ref "SPC") (pin "1") (pinfunction "1_1") (pintype "passive"))
    )
    (net (code "54") (name "Net-(IC7A-A2)") (class "Default")
      (node (ref "IC7") (pin "4") (pinfunction "A2_4") (pintype "input"))
      (node (ref "SYM") (pin "1") (pinfunction "1_1") (pintype "passive"))
    )
    (net (code "55") (name "Net-(IC7A-A3)") (class "Default")
      (node (ref "IC7") (pin "6") (pinfunction "A3_6") (pintype "input"))
      (node (ref "M") (pin "1") (pinfunction "1_1") (pintype "passive"))
    )
    (net (code "56") (name "Net-(IC7A-A4)") (class "Default")
      (node (ref "IC7") (pin "10") (pinfunction "A4_10") (pintype "input"))
      (node (ref "N") (pin "1") (pinfunction "1_1") (pintype "passive"))
    )
    (net (code "57") (name "Net-(IC7A-A5)") (class "Default")
      (node (ref "B") (pin "1") (pinfunction "1_1") (pintype "passive"))
      (node (ref "IC7") (pin "12") (pinfunction "A5_12") (pintype "input"))
    )
    (net (code "58") (name "Net-(IC7A-Y1)") (class "Default")
      (node (ref "D1") (pin "C") (pinfunction "C_C") (pintype "passive"))
      (node (ref "IC7") (pin "3") (pinfunction "Y1_3") (pintype "tri_state"))
    )
    (net (code "59") (name "Net-(IC7A-Y2)") (class "Default")
      (node (ref "D2") (pin "C") (pinfunction "C_C") (pintype "passive"))
      (node (ref "IC7") (pin "5") (pinfunction "Y2_5") (pintype "tri_state"))
    )
    (net (code "60") (name "Net-(IC7A-Y3)") (class "Default")
      (node (ref "D3") (pin "C") (pinfunction "C_C") (pintype "passive"))
      (node (ref "IC7") (pin "7") (pinfunction "Y3_7") (pintype "tri_state"))
    )
    (net (code "61") (name "Net-(IC7A-Y4)") (class "Default")
      (node (ref "D4") (pin "C") (pinfunction "C_C") (pintype "passive"))
      (node (ref "IC7") (pin "9") (pinfunction "Y4_9") (pintype "tri_state"))
    )
    (net (code "62") (name "Net-(IC7A-Y5)") (class "Default")
      (node (ref "D5") (pin "C") (pinfunction "C_C") (pintype "passive"))
      (node (ref "IC7") (pin "11") (pinfunction "Y5_11") (pintype "tri_state"))
    )
    (net (code "63") (name "Net-(IC8A-A1)") (class "Default")
      (node (ref "CAP") (pin "1") (pinfunction "1_1") (pintype "passive"))
      (node (ref "IC8") (pin "2") (pinfunction "A1_2") (pintype "input"))
    )
    (net (code "64") (name "Net-(IC8A-A2)") (class "Default")
      (node (ref "IC8") (pin "4") (pinfunction "A2_4") (pintype "input"))
      (node (ref "Z") (pin "1") (pinfunction "1_1") (pintype "passive"))
    )
    (net (code "65") (name "Net-(IC8A-A3)") (class "Default")
      (node (ref "IC8") (pin "6") (pinfunction "A3_6") (pintype "input"))
      (node (ref "X") (pin "1") (pinfunction "1_1") (pintype "passive"))
    )
    (net (code "66") (name "Net-(IC8A-A4)") (class "Default")
      (node (ref "C") (pin "1") (pinfunction "1_1") (pintype "passive"))
      (node (ref "IC8") (pin "10") (pinfunction "A4_10") (pintype "input"))
    )
    (net (code "67") (name "Net-(IC8A-A5)") (class "Default")
      (node (ref "IC8") (pin "12") (pinfunction "A5_12") (pintype "input"))
      (node (ref "V") (pin "1") (pinfunction "1_1") (pintype "passive"))
    )
    (net (code "68") (name "Net-(IC8A-Y1)") (class "Default")
      (node (ref "D6") (pin "C") (pinfunction "C_C") (pintype "passive"))
      (node (ref "IC8") (pin "3") (pinfunction "Y1_3") (pintype "tri_state"))
    )
    (net (code "69") (name "Net-(IC8A-Y2)") (class "Default")
      (node (ref "D7") (pin "C") (pinfunction "C_C") (pintype "passive"))
      (node (ref "IC8") (pin "5") (pinfunction "Y2_5") (pintype "tri_state"))
    )
    (net (code "70") (name "Net-(IC8A-Y3)") (class "Default")
      (node (ref "D8") (pin "C") (pinfunction "C_C") (pintype "passive"))
      (node (ref "IC8") (pin "7") (pinfunction "Y3_7") (pintype "tri_state"))
    )
    (net (code "71") (name "Net-(IC8A-Y4)") (class "Default")
      (node (ref "D9") (pin "C") (pinfunction "C_C") (pintype "passive"))
      (node (ref "IC8") (pin "9") (pinfunction "Y4_9") (pintype "tri_state"))
    )
    (net (code "72") (name "Net-(IC8A-Y5)") (class "Default")
      (node (ref "D10") (pin "C") (pinfunction "C_C") (pintype "passive"))
      (node (ref "IC8") (pin "11") (pinfunction "Y5_11") (pintype "tri_state"))
    )
    (net (code "73") (name "Net-(IC9A-A1)") (class "Default")
      (node (ref "ENT") (pin "1") (pinfunction "1_1") (pintype "passive"))
      (node (ref "IC9") (pin "2") (pinfunction "A1_2") (pintype "input"))
    )
    (net (code "74") (name "Net-(IC9A-A2)") (class "Default")
      (node (ref "IC9") (pin "4") (pinfunction "A2_4") (pintype "input"))
      (node (ref "L") (pin "1") (pinfunction "1_1") (pintype "passive"))
    )
    (net (code "75") (name "Net-(IC9A-A3)") (class "Default")
      (node (ref "IC9") (pin "6") (pinfunction "A3_6") (pintype "input"))
      (node (ref "K") (pin "1") (pinfunction "1_1") (pintype "passive"))
    )
    (net (code "76") (name "Net-(IC9A-A4)") (class "Default")
      (node (ref "IC9") (pin "10") (pinfunction "A4_10") (pintype "input"))
      (node (ref "J") (pin "1") (pinfunction "1_1") (pintype "passive"))
    )
    (net (code "77") (name "Net-(IC9A-A5)") (class "Default")
      (node (ref "H") (pin "1") (pinfunction "1_1") (pintype "passive"))
      (node (ref "IC9") (pin "12") (pinfunction "A5_12") (pintype "input"))
    )
    (net (code "78") (name "Net-(IC9A-Y1)") (class "Default")
      (node (ref "D11") (pin "C") (pinfunction "C_C") (pintype "passive"))
      (node (ref "IC9") (pin "3") (pinfunction "Y1_3") (pintype "tri_state"))
    )
    (net (code "79") (name "Net-(IC9A-Y2)") (class "Default")
      (node (ref "D12") (pin "C") (pinfunction "C_C") (pintype "passive"))
      (node (ref "IC9") (pin "5") (pinfunction "Y2_5") (pintype "tri_state"))
    )
    (net (code "80") (name "Net-(IC9A-Y3)") (class "Default")
      (node (ref "D13") (pin "C") (pinfunction "C_C") (pintype "passive"))
      (node (ref "IC9") (pin "7") (pinfunction "Y3_7") (pintype "tri_state"))
    )
    (net (code "81") (name "Net-(IC9A-Y4)") (class "Default")
      (node (ref "D14") (pin "C") (pinfunction "C_C") (pintype "passive"))
      (node (ref "IC9") (pin "9") (pinfunction "Y4_9") (pintype "tri_state"))
    )
    (net (code "82") (name "Net-(IC9A-Y5)") (class "Default")
      (node (ref "D15") (pin "C") (pinfunction "C_C") (pintype "passive"))
      (node (ref "IC9") (pin "11") (pinfunction "Y5_11") (pintype "tri_state"))
    )
    (net (code "83") (name "Net-(IC10A-A1)") (class "Default")
      (node (ref "A") (pin "1") (pinfunction "1_1") (pintype "passive"))
      (node (ref "IC10") (pin "2") (pinfunction "A1_2") (pintype "input"))
    )
    (net (code "84") (name "Net-(IC10A-A2)") (class "Default")
      (node (ref "IC10") (pin "4") (pinfunction "A2_4") (pintype "input"))
      (node (ref "S") (pin "1") (pinfunction "1_1") (pintype "passive"))
    )
    (net (code "85") (name "Net-(IC10A-A3)") (class "Default")
      (node (ref "D") (pin "1") (pinfunction "1_1") (pintype "passive"))
      (node (ref "IC10") (pin "6") (pinfunction "A3_6") (pintype "input"))
    )
    (net (code "86") (name "Net-(IC10A-A4)") (class "Default")
      (node (ref "F") (pin "1") (pinfunction "1_1") (pintype "passive"))
      (node (ref "IC10") (pin "10") (pinfunction "A4_10") (pintype "input"))
    )
    (net (code "87") (name "Net-(IC10A-A5)") (class "Default")
      (node (ref "G") (pin "1") (pinfunction "1_1") (pintype "passive"))
      (node (ref "IC10") (pin "12") (pinfunction "A5_12") (pintype "input"))
    )
    (net (code "88") (name "Net-(IC10A-Y1)") (class "Default")
      (node (ref "D16") (pin "C") (pinfunction "C_C") (pintype "passive"))
      (node (ref "IC10") (pin "3") (pinfunction "Y1_3") (pintype "tri_state"))
    )
    (net (code "89") (name "Net-(IC10A-Y2)") (class "Default")
      (node (ref "D17") (pin "C") (pinfunction "C_C") (pintype "passive"))
      (node (ref "IC10") (pin "5") (pinfunction "Y2_5") (pintype "tri_state"))
    )
    (net (code "90") (name "Net-(IC10A-Y3)") (class "Default")
      (node (ref "D18") (pin "C") (pinfunction "C_C") (pintype "passive"))
      (node (ref "IC10") (pin "7") (pinfunction "Y3_7") (pintype "tri_state"))
    )
    (net (code "91") (name "Net-(IC10A-Y4)") (class "Default")
      (node (ref "D19") (pin "C") (pinfunction "C_C") (pintype "passive"))
      (node (ref "IC10") (pin "9") (pinfunction "Y4_9") (pintype "tri_state"))
    )
    (net (code "92") (name "Net-(IC10A-Y5)") (class "Default")
      (node (ref "D20") (pin "C") (pinfunction "C_C") (pintype "passive"))
      (node (ref "IC10") (pin "11") (pinfunction "Y5_11") (pintype "tri_state"))
    )
    (net (code "93") (name "Net-(IC11A-A1)") (class "Default")
      (node (ref "IC11") (pin "2") (pinfunction "A1_2") (pintype "input"))
      (node (ref "P") (pin "1") (pinfunction "1_1") (pintype "passive"))
    )
    (net (code "94") (name "Net-(IC11A-A2)") (class "Default")
      (node (ref "IC11") (pin "4") (pinfunction "A2_4") (pintype "input"))
      (node (ref "O") (pin "1") (pinfunction "1_1") (pintype "passive"))
    )
    (net (code "95") (name "Net-(IC11A-A3)") (class "Default")
      (node (ref "I") (pin "1") (pinfunction "1_1") (pintype "passive"))
      (node (ref "IC11") (pin "6") (pinfunction "A3_6") (pintype "input"))
    )
    (net (code "96") (name "Net-(IC11A-A4)") (class "Default")
      (node (ref "IC11") (pin "10") (pinfunction "A4_10") (pintype "input"))
      (node (ref "U") (pin "1") (pinfunction "1_1") (pintype "passive"))
    )
    (net (code "97") (name "Net-(IC11A-A5)") (class "Default")
      (node (ref "IC11") (pin "12") (pinfunction "A5_12") (pintype "input"))
      (node (ref "Y") (pin "1") (pinfunction "1_1") (pintype "passive"))
    )
    (net (code "98") (name "Net-(IC11A-Y1)") (class "Default")
      (node (ref "D21") (pin "C") (pinfunction "C_C") (pintype "passive"))
      (node (ref "IC11") (pin "3") (pinfunction "Y1_3") (pintype "tri_state"))
    )
    (net (code "99") (name "Net-(IC11A-Y2)") (class "Default")
      (node (ref "D22") (pin "C") (pinfunction "C_C") (pintype "passive"))
      (node (ref "IC11") (pin "5") (pinfunction "Y2_5") (pintype "tri_state"))
    )
    (net (code "100") (name "Net-(IC11A-Y3)") (class "Default")
      (node (ref "D23") (pin "C") (pinfunction "C_C") (pintype "passive"))
      (node (ref "IC11") (pin "7") (pinfunction "Y3_7") (pintype "tri_state"))
    )
    (net (code "101") (name "Net-(IC11A-Y4)") (class "Default")
      (node (ref "D24") (pin "C") (pinfunction "C_C") (pintype "passive"))
      (node (ref "IC11") (pin "9") (pinfunction "Y4_9") (pintype "tri_state"))
    )
    (net (code "102") (name "Net-(IC11A-Y5)") (class "Default")
      (node (ref "D25") (pin "C") (pinfunction "C_C") (pintype "passive"))
      (node (ref "IC11") (pin "11") (pinfunction "Y5_11") (pintype "tri_state"))
    )
    (net (code "103") (name "Net-(IC12A-A1)") (class "Default")
      (node (ref "IC12") (pin "2") (pinfunction "A1_2") (pintype "input"))
      (node (ref "Q") (pin "1") (pinfunction "1_1") (pintype "passive"))
    )
    (net (code "104") (name "Net-(IC12A-A2)") (class "Default")
      (node (ref "IC12") (pin "4") (pinfunction "A2_4") (pintype "input"))
      (node (ref "W") (pin "1") (pinfunction "1_1") (pintype "passive"))
    )
    (net (code "105") (name "Net-(IC12A-A3)") (class "Default")
      (node (ref "E") (pin "1") (pinfunction "1_1") (pintype "passive"))
      (node (ref "IC12") (pin "6") (pinfunction "A3_6") (pintype "input"))
    )
    (net (code "106") (name "Net-(IC12A-A4)") (class "Default")
      (node (ref "IC12") (pin "10") (pinfunction "A4_10") (pintype "input"))
      (node (ref "R") (pin "1") (pinfunction "1_1") (pintype "passive"))
    )
    (net (code "107") (name "Net-(IC12A-A5)") (class "Default")
      (node (ref "IC12") (pin "12") (pinfunction "A5_12") (pintype "input"))
      (node (ref "T") (pin "1") (pinfunction "1_1") (pintype "passive"))
    )
    (net (code "108") (name "Net-(IC12A-Y1)") (class "Default")
      (node (ref "D26") (pin "C") (pinfunction "C_C") (pintype "passive"))
      (node (ref "IC12") (pin "3") (pinfunction "Y1_3") (pintype "tri_state"))
    )
    (net (code "109") (name "Net-(IC12A-Y2)") (class "Default")
      (node (ref "D27") (pin "C") (pinfunction "C_C") (pintype "passive"))
      (node (ref "IC12") (pin "5") (pinfunction "Y2_5") (pintype "tri_state"))
    )
    (net (code "110") (name "Net-(IC12A-Y3)") (class "Default")
      (node (ref "D28") (pin "C") (pinfunction "C_C") (pintype "passive"))
      (node (ref "IC12") (pin "7") (pinfunction "Y3_7") (pintype "tri_state"))
    )
    (net (code "111") (name "Net-(IC12A-Y4)") (class "Default")
      (node (ref "D29") (pin "C") (pinfunction "C_C") (pintype "passive"))
      (node (ref "IC12") (pin "9") (pinfunction "Y4_9") (pintype "tri_state"))
    )
    (net (code "112") (name "Net-(IC12A-Y5)") (class "Default")
      (node (ref "D30") (pin "C") (pinfunction "C_C") (pintype "passive"))
      (node (ref "IC12") (pin "11") (pinfunction "Y5_11") (pintype "tri_state"))
    )
    (net (code "113") (name "Net-(IC13A-A1)") (class "Default")
      (node (ref "0") (pin "1") (pinfunction "1_1") (pintype "passive"))
      (node (ref "IC13") (pin "2") (pinfunction "A1_2") (pintype "input"))
    )
    (net (code "114") (name "Net-(IC13A-A2)") (class "Default")
      (node (ref "9") (pin "1") (pinfunction "1_1") (pintype "passive"))
      (node (ref "IC13") (pin "4") (pinfunction "A2_4") (pintype "input"))
    )
    (net (code "115") (name "Net-(IC13A-A3)") (class "Default")
      (node (ref "8") (pin "1") (pinfunction "1_1") (pintype "passive"))
      (node (ref "IC13") (pin "6") (pinfunction "A3_6") (pintype "input"))
    )
    (net (code "116") (name "Net-(IC13A-A4)") (class "Default")
      (node (ref "7") (pin "1") (pinfunction "1_1") (pintype "passive"))
      (node (ref "IC13") (pin "10") (pinfunction "A4_10") (pintype "input"))
    )
    (net (code "117") (name "Net-(IC13A-A5)") (class "Default")
      (node (ref "6") (pin "1") (pinfunction "1_1") (pintype "passive"))
      (node (ref "IC13") (pin "12") (pinfunction "A5_12") (pintype "input"))
    )
    (net (code "118") (name "Net-(IC13A-Y1)") (class "Default")
      (node (ref "D31") (pin "C") (pinfunction "C_C") (pintype "passive"))
      (node (ref "IC13") (pin "3") (pinfunction "Y1_3") (pintype "tri_state"))
    )
    (net (code "119") (name "Net-(IC13A-Y2)") (class "Default")
      (node (ref "D32") (pin "C") (pinfunction "C_C") (pintype "passive"))
      (node (ref "IC13") (pin "5") (pinfunction "Y2_5") (pintype "tri_state"))
    )
    (net (code "120") (name "Net-(IC13A-Y3)") (class "Default")
      (node (ref "D33") (pin "C") (pinfunction "C_C") (pintype "passive"))
      (node (ref "IC13") (pin "7") (pinfunction "Y3_7") (pintype "tri_state"))
    )
    (net (code "121") (name "Net-(IC13A-Y4)") (class "Default")
      (node (ref "D34") (pin "C") (pinfunction "C_C") (pintype "passive"))
      (node (ref "IC13") (pin "9") (pinfunction "Y4_9") (pintype "tri_state"))
    )
    (net (code "122") (name "Net-(IC13A-Y5)") (class "Default")
      (node (ref "D35") (pin "C") (pinfunction "C_C") (pintype "passive"))
      (node (ref "IC13") (pin "11") (pinfunction "Y5_11") (pintype "tri_state"))
    )
    (net (code "123") (name "Net-(IC14A-A1)") (class "Default")
      (node (ref "1") (pin "1") (pinfunction "1_1") (pintype "passive"))
      (node (ref "IC14") (pin "2") (pinfunction "A1_2") (pintype "input"))
    )
    (net (code "124") (name "Net-(IC14A-A2)") (class "Default")
      (node (ref "2") (pin "1") (pinfunction "1_1") (pintype "passive"))
      (node (ref "IC14") (pin "4") (pinfunction "A2_4") (pintype "input"))
    )
    (net (code "125") (name "Net-(IC14A-A3)") (class "Default")
      (node (ref "3") (pin "1") (pinfunction "1_1") (pintype "passive"))
      (node (ref "IC14") (pin "6") (pinfunction "A3_6") (pintype "input"))
    )
    (net (code "126") (name "Net-(IC14A-A4)") (class "Default")
      (node (ref "4") (pin "1") (pinfunction "1_1") (pintype "passive"))
      (node (ref "IC14") (pin "10") (pinfunction "A4_10") (pintype "input"))
    )
    (net (code "127") (name "Net-(IC14A-A5)") (class "Default")
      (node (ref "5") (pin "1") (pinfunction "1_1") (pintype "passive"))
      (node (ref "IC14") (pin "12") (pinfunction "A5_12") (pintype "input"))
    )
    (net (code "128") (name "Net-(IC14A-Y1)") (class "Default")
      (node (ref "D36") (pin "C") (pinfunction "C_C") (pintype "passive"))
      (node (ref "IC14") (pin "3") (pinfunction "Y1_3") (pintype "tri_state"))
    )
    (net (code "129") (name "Net-(IC14A-Y2)") (class "Default")
      (node (ref "D37") (pin "C") (pinfunction "C_C") (pintype "passive"))
      (node (ref "IC14") (pin "5") (pinfunction "Y2_5") (pintype "tri_state"))
    )
    (net (code "130") (name "Net-(IC14A-Y3)") (class "Default")
      (node (ref "D38") (pin "C") (pinfunction "C_C") (pintype "passive"))
      (node (ref "IC14") (pin "7") (pinfunction "Y3_7") (pintype "tri_state"))
    )
    (net (code "131") (name "Net-(IC14A-Y4)") (class "Default")
      (node (ref "D39") (pin "C") (pinfunction "C_C") (pintype "passive"))
      (node (ref "IC14") (pin "9") (pinfunction "Y4_9") (pintype "tri_state"))
    )
    (net (code "132") (name "Net-(IC14A-Y5)") (class "Default")
      (node (ref "D40") (pin "C") (pinfunction "C_C") (pintype "passive"))
      (node (ref "IC14") (pin "11") (pinfunction "Y5_11") (pintype "tri_state"))
    )
    (net (code "133") (name "Net-(LEFTJ1-Pad1)") (class "Default")
      (node (ref "LEFTJ1") (pin "1") (pinfunction "1_1") (pintype "passive"))
      (node (ref "X1") (pin "3") (pinfunction "3_3") (pintype "passive"))
    )
    (net (code "134") (name "Net-(LEFTJ2-Pad1)") (class "Default")
      (node (ref "LEFTJ2") (pin "1") (pinfunction "1_1") (pintype "passive"))
      (node (ref "X2") (pin "3") (pinfunction "3_3") (pintype "passive"))
    )
    (net (code "135") (name "Net-(LEFTJ3-Pad1)") (class "Default")
      (node (ref "LEFTJ3") (pin "1") (pinfunction "1_1") (pintype "passive"))
      (node (ref "X3") (pin "3") (pinfunction "3_3") (pintype "passive"))
    )
    (net (code "136") (name "Net-(LEFTJ4-Pad1)") (class "Default")
      (node (ref "LEFTJ4") (pin "1") (pinfunction "1_1") (pintype "passive"))
      (node (ref "X4") (pin "3") (pinfunction "3_3") (pintype "passive"))
    )
    (net (code "137") (name "Net-(PIN5J1-Pad1)") (class "Default")
      (node (ref "PIN5J1") (pin "1") (pinfunction "1_1") (pintype "passive"))
      (node (ref "X1") (pin "5") (pinfunction "5_5") (pintype "passive"))
    )
    (net (code "138") (name "Net-(PIN5J2-Pad1)") (class "Default")
      (node (ref "PIN5J2") (pin "1") (pinfunction "1_1") (pintype "passive"))
      (node (ref "X2") (pin "5") (pinfunction "5_5") (pintype "passive"))
    )
    (net (code "139") (name "Net-(PIN5J3-Pad1)") (class "Default")
      (node (ref "PIN5J3") (pin "1") (pinfunction "1_1") (pintype "passive"))
      (node (ref "X3") (pin "5") (pinfunction "5_5") (pintype "passive"))
    )
    (net (code "140") (name "Net-(PIN5J4-Pad1)") (class "Default")
      (node (ref "PIN5J4") (pin "1") (pinfunction "1_1") (pintype "passive"))
      (node (ref "X4") (pin "5") (pinfunction "5_5") (pintype "passive"))
    )
    (net (code "141") (name "Net-(PIN7J1-Pad1)") (class "Default")
      (node (ref "PIN7J1") (pin "1") (pinfunction "1_1") (pintype "passive"))
      (node (ref "X1") (pin "7") (pinfunction "7_7") (pintype "passive"))
    )
    (net (code "142") (name "Net-(PIN7J2-Pad1)") (class "Default")
      (node (ref "PIN7J2") (pin "1") (pinfunction "1_1") (pintype "passive"))
      (node (ref "X2") (pin "7") (pinfunction "7_7") (pintype "passive"))
    )
    (net (code "143") (name "Net-(PIN7J3-Pad1)") (class "Default")
      (node (ref "PIN7J3") (pin "1") (pinfunction "1_1") (pintype "passive"))
      (node (ref "X3") (pin "7") (pinfunction "7_7") (pintype "passive"))
    )
    (net (code "144") (name "Net-(PIN7J4-Pad1)") (class "Default")
      (node (ref "PIN7J4") (pin "1") (pinfunction "1_1") (pintype "passive"))
      (node (ref "X4") (pin "7") (pinfunction "7_7") (pintype "passive"))
    )
    (net (code "145") (name "Net-(PIN9J1-Pad1)") (class "Default")
      (node (ref "PIN9J1") (pin "1") (pinfunction "1_1") (pintype "passive"))
      (node (ref "X1") (pin "9") (pinfunction "9_9") (pintype "passive"))
    )
    (net (code "146") (name "Net-(PIN9J2-Pad1)") (class "Default")
      (node (ref "PIN9J2") (pin "1") (pinfunction "1_1") (pintype "passive"))
      (node (ref "X2") (pin "9") (pinfunction "9_9") (pintype "passive"))
    )
    (net (code "147") (name "Net-(PIN9J3-Pad1)") (class "Default")
      (node (ref "PIN9J3") (pin "1") (pinfunction "1_1") (pintype "passive"))
      (node (ref "X3") (pin "9") (pinfunction "9_9") (pintype "passive"))
    )
    (net (code "148") (name "Net-(PIN9J4-Pad1)") (class "Default")
      (node (ref "PIN9J4") (pin "1") (pinfunction "1_1") (pintype "passive"))
      (node (ref "X4") (pin "9") (pinfunction "9_9") (pintype "passive"))
    )
    (net (code "149") (name "Net-(RIGHTJ1-Pad1)") (class "Default")
      (node (ref "RIGHTJ1") (pin "1") (pinfunction "1_1") (pintype "passive"))
      (node (ref "X1") (pin "4") (pinfunction "4_4") (pintype "passive"))
    )
    (net (code "150") (name "Net-(RIGHTJ2-Pad1)") (class "Default")
      (node (ref "RIGHTJ2") (pin "1") (pinfunction "1_1") (pintype "passive"))
      (node (ref "X2") (pin "4") (pinfunction "4_4") (pintype "passive"))
    )
    (net (code "151") (name "Net-(RIGHTJ3-Pad1)") (class "Default")
      (node (ref "RIGHTJ3") (pin "1") (pinfunction "1_1") (pintype "passive"))
      (node (ref "X3") (pin "4") (pinfunction "4_4") (pintype "passive"))
    )
    (net (code "152") (name "Net-(RIGHTJ4-Pad1)") (class "Default")
      (node (ref "RIGHTJ4") (pin "1") (pinfunction "1_1") (pintype "passive"))
      (node (ref "X4") (pin "4") (pinfunction "4_4") (pintype "passive"))
    )
    (net (code "153") (name "Net-(UPJ1-Pad1)") (class "Default")
      (node (ref "UPJ1") (pin "1") (pinfunction "1_1") (pintype "passive"))
      (node (ref "X1") (pin "1") (pinfunction "1_1") (pintype "passive"))
    )
    (net (code "154") (name "Net-(UPJ2-Pad1)") (class "Default")
      (node (ref "UPJ2") (pin "1") (pinfunction "1_1") (pintype "passive"))
      (node (ref "X2") (pin "1") (pinfunction "1_1") (pintype "passive"))
    )
    (net (code "155") (name "Net-(UPJ3-Pad1)") (class "Default")
      (node (ref "UPJ3") (pin "1") (pinfunction "1_1") (pintype "passive"))
      (node (ref "X3") (pin "1") (pinfunction "1_1") (pintype "passive"))
    )
    (net (code "156") (name "Net-(UPJ4-Pad1)") (class "Default")
      (node (ref "UPJ4") (pin "1") (pinfunction "1_1") (pintype "passive"))
      (node (ref "X4") (pin "1") (pinfunction "1_1") (pintype "passive"))
    )
    (net (code "157") (name "VCC") (class "Default")
      (node (ref "C1") (pin "1") (pinfunction "1_1") (pintype "passive"))
      (node (ref "C10") (pin "1") (pinfunction "1_1") (pintype "passive"))
      (node (ref "C2") (pin "1") (pinfunction "1_1") (pintype "passive"))
      (node (ref "C3") (pin "1") (pinfunction "1_1") (pintype "passive"))
      (node (ref "C4") (pin "1") (pinfunction "1_1") (pintype "passive"))
      (node (ref "C5") (pin "1") (pinfunction "1_1") (pintype "passive"))
      (node (ref "C6") (pin "1") (pinfunction "1_1") (pintype "passive"))
      (node (ref "C7") (pin "1") (pinfunction "1_1") (pintype "passive"))
      (node (ref "C8") (pin "1") (pinfunction "1_1") (pintype "passive"))
      (node (ref "C9") (pin "1") (pinfunction "1_1") (pintype "passive"))
      (node (ref "IC2") (pin "14") (pinfunction "A6_14") (pintype "input"))
      (node (ref "U$1") (pin "+5V") (pinfunction "+5V_+5V") (pintype "bidirectional"))
      (node (ref "U$3") (pin "A3") (pinfunction "5V_A3") (pintype "power_in"))
      (node (ref "VCCJ1") (pin "1") (pinfunction "1_1") (pintype "passive"))
      (node (ref "VCCJ2") (pin "1") (pinfunction "1_1") (pintype "passive"))
    )
    (net (code "158") (name "unconnected-(IC7A-A6-Pad14)") (class "Default")
      (node (ref "IC7") (pin "14") (pinfunction "A6_14") (pintype "input"))
    )
    (net (code "159") (name "unconnected-(IC7A-Y6-Pad13)") (class "Default")
      (node (ref "IC7") (pin "13") (pinfunction "Y6_13") (pintype "tri_state"))
    )
    (net (code "160") (name "unconnected-(IC8A-A6-Pad14)") (class "Default")
      (node (ref "IC8") (pin "14") (pinfunction "A6_14") (pintype "input"))
    )
    (net (code "161") (name "unconnected-(IC8A-Y6-Pad13)") (class "Default")
      (node (ref "IC8") (pin "13") (pinfunction "Y6_13") (pintype "tri_state"))
    )
    (net (code "162") (name "unconnected-(IC9A-A6-Pad14)") (class "Default")
      (node (ref "IC9") (pin "14") (pinfunction "A6_14") (pintype "input"))
    )
    (net (code "163") (name "unconnected-(IC9A-Y6-Pad13)") (class "Default")
      (node (ref "IC9") (pin "13") (pinfunction "Y6_13") (pintype "tri_state"))
    )
    (net (code "164") (name "unconnected-(IC10A-A6-Pad14)") (class "Default")
      (node (ref "IC10") (pin "14") (pinfunction "A6_14") (pintype "input"))
    )
    (net (code "165") (name "unconnected-(IC10A-Y6-Pad13)") (class "Default")
      (node (ref "IC10") (pin "13") (pinfunction "Y6_13") (pintype "tri_state"))
    )
    (net (code "166") (name "unconnected-(IC11A-A6-Pad14)") (class "Default")
      (node (ref "IC11") (pin "14") (pinfunction "A6_14") (pintype "input"))
    )
    (net (code "167") (name "unconnected-(IC11A-Y6-Pad13)") (class "Default")
      (node (ref "IC11") (pin "13") (pinfunction "Y6_13") (pintype "tri_state"))
    )
    (net (code "168") (name "unconnected-(IC12A-A6-Pad14)") (class "Default")
      (node (ref "IC12") (pin "14") (pinfunction "A6_14") (pintype "input"))
    )
    (net (code "169") (name "unconnected-(IC12A-Y6-Pad13)") (class "Default")
      (node (ref "IC12") (pin "13") (pinfunction "Y6_13") (pintype "tri_state"))
    )
    (net (code "170") (name "unconnected-(IC13A-A6-Pad14)") (class "Default")
      (node (ref "IC13") (pin "14") (pinfunction "A6_14") (pintype "input"))
    )
    (net (code "171") (name "unconnected-(IC13A-Y6-Pad13)") (class "Default")
      (node (ref "IC13") (pin "13") (pinfunction "Y6_13") (pintype "tri_state"))
    )
    (net (code "172") (name "unconnected-(IC14A-A6-Pad14)") (class "Default")
      (node (ref "IC14") (pin "14") (pinfunction "A6_14") (pintype "input"))
    )
    (net (code "173") (name "unconnected-(IC14A-Y6-Pad13)") (class "Default")
      (node (ref "IC14") (pin "13") (pinfunction "Y6_13") (pintype "tri_state"))
    )
    (net (code "174") (name "unconnected-(U$3-CK-PadA8)") (class "Default")
      (node (ref "U$3") (pin "A8") (pinfunction "CK_A8") (pintype "bidirectional"))
    )
    (net (code "175") (name "unconnected-(U$3-NC-PadB4)") (class "Default")
      (node (ref "U$3") (pin "B4") (pinfunction "NC_B4") (pintype "no_connect"))
    )
    (net (code "176") (name "unconnected-(U$3-NC2-PadB28)") (class "Default")
      (node (ref "U$3") (pin "B28") (pinfunction "NC2_B28") (pintype "no_connect"))
    )
    (net (code "177") (name "unconnected-(U$3-U-PadA18)") (class "Default")
      (node (ref "U$3") (pin "A18") (pinfunction "U_A18") (pintype "bidirectional"))
    )
    (net (code "178") (name "unconnected-(U$3-V-PadA17)") (class "Default")
      (node (ref "U$3") (pin "A17") (pinfunction "V_A17") (pintype "bidirectional"))
    )
    (net (code "179") (name "unconnected-(U$3-VIDEO-PadA15)") (class "Default")
      (node (ref "U$3") (pin "A15") (pinfunction "VIDEO_A15") (pintype "bidirectional"))
    )
    (net (code "180") (name "unconnected-(U$3-{slash}BUSACK-PadA26)") (class "Default")
      (node (ref "U$3") (pin "A26") (pinfunction "/BUSACK_A26") (pintype "bidirectional"))
    )
    (net (code "181") (name "unconnected-(U$3-{slash}BUSRQ-PadA19)") (class "Default")
      (node (ref "U$3") (pin "A19") (pinfunction "/BUSRQ_A19") (pintype "bidirectional"))
    )
    (net (code "182") (name "unconnected-(U$3-{slash}HALT-PadB15)") (class "Default")
      (node (ref "U$3") (pin "B15") (pinfunction "/HALT_B15") (pintype "bidirectional"))
    )
    (net (code "183") (name "unconnected-(U$3-{slash}INT-PadB13)") (class "Default")
      (node (ref "U$3") (pin "B13") (pinfunction "/INT_B13") (pintype "bidirectional"))
    )
    (net (code "184") (name "unconnected-(U$3-{slash}IORQ_ULA-PadA13)") (class "Default")
      (node (ref "U$3") (pin "A13") (pinfunction "/IORQ_ULA_A13") (pintype "bidirectional"))
    )
    (net (code "185") (name "unconnected-(U$3-{slash}M1-PadB24)") (class "Default")
      (node (ref "U$3") (pin "B24") (pinfunction "/M1_B24") (pintype "bidirectional"))
    )
    (net (code "186") (name "unconnected-(U$3-{slash}NMI-PadB14)") (class "Default")
      (node (ref "U$3") (pin "B14") (pinfunction "/NMI_B14") (pintype "bidirectional"))
    )
    (net (code "187") (name "unconnected-(U$3-{slash}RESET-PadA20)") (class "Default")
      (node (ref "U$3") (pin "A20") (pinfunction "/RESET_A20") (pintype "bidirectional"))
    )
    (net (code "188") (name "unconnected-(U$3-{slash}RFSH-PadB25)") (class "Default")
      (node (ref "U$3") (pin "B25") (pinfunction "/RFSH_B25") (pintype "bidirectional"))
    )
    (net (code "189") (name "unconnected-(U$3-{slash}WAIT-PadB21)") (class "Default")
      (node (ref "U$3") (pin "B21") (pinfunction "/WAIT_B21") (pintype "bidirectional"))
    )
    (net (code "190") (name "unconnected-(U$3-{slash}Y-PadA16)") (class "Default")
      (node (ref "U$3") (pin "A16") (pinfunction "/Y_A16") (pintype "bidirectional"))
    )
  )
)
